# Communication_USB_-_FT232.net
KiCad netlist of a schematic drawn in Altium Designer
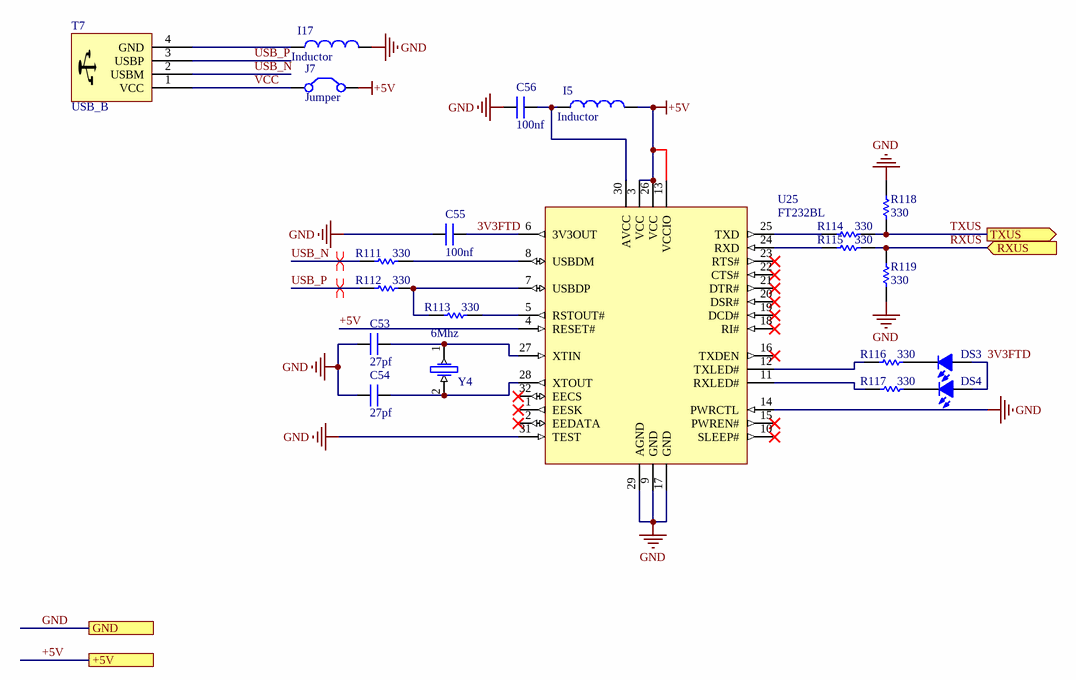
[diagram p0: Communication USB - FT232.SchDoc]

(export (version "E")
  (design (tool "Eeschema 10.0.6"))
  (components
    (comp (ref "C53")
      (value "27pf")
      (footprint "Cap0805")
      (description "Surface mount Capacitor")
      (libsource (lib "PMLIB2020") (part "Cap"))
    )
    (comp (ref "C54")
      (value "27pf")
      (footprint "Cap0805")
      (description "Surface mount Capacitor")
      (libsource (lib "PMLIB2020") (part "Cap"))
    )
    (comp (ref "C55")
      (value "100nf")
      (footprint "Cap0805")
      (description "Surface mount Capacitor")
      (libsource (lib "PMLIB2020") (part "Cap"))
    )
    (comp (ref "C56")
      (value "100nf")
      (footprint "Cap0805")
      (description "Surface mount Capacitor")
      (libsource (lib "PMLIB2020") (part "Cap"))
    )
    (comp (ref "DS3") (value "LED") (footprint "Led0805") (libsource (lib "PMLIB2020") (part "LED")))
    (comp (ref "DS4") (value "LED") (footprint "Led0805") (libsource (lib "PMLIB2020") (part "LED")))
    (comp (ref "I5")
      (value "Inductor")
      (footprint "1206")
      (description "Indicator")
      (libsource (lib "PMLIB2020") (part "Inductor"))
    )
    (comp (ref "I17")
      (value "Inductor")
      (footprint "1206")
      (description "Indicator")
      (libsource (lib "PMLIB2020") (part "Inductor"))
    )
    (comp (ref "J7") (value "Jumper") (footprint "Jumper") (libsource (lib "PMLIB2020-V3") (part "Jumper")))
    (comp (ref "R111")
      (value "330")
      (footprint "R0805")
      (description "Resistor")
      (libsource (lib "PMLIB2020") (part "Resistor"))
    )
    (comp (ref "R112")
      (value "330")
      (footprint "R0805")
      (description "Resistor")
      (libsource (lib "PMLIB2020") (part "Resistor"))
    )
    (comp (ref "R113")
      (value "330")
      (footprint "R0805")
      (description "Resistor")
      (libsource (lib "PMLIB2020") (part "Resistor"))
    )
    (comp (ref "R114")
      (value "330")
      (footprint "R0805")
      (description "Resistor")
      (libsource (lib "PMLIB2020") (part "Resistor"))
    )
    (comp (ref "R115")
      (value "330")
      (footprint "R0805")
      (description "Resistor")
      (libsource (lib "PMLIB2020") (part "Resistor"))
    )
    (comp (ref "R116")
      (value "330")
      (footprint "R0805")
      (description "Resistor")
      (libsource (lib "PMLIB2020") (part "Resistor"))
    )
    (comp (ref "R117")
      (value "330")
      (footprint "R0805")
      (description "Resistor")
      (libsource (lib "PMLIB2020") (part "Resistor"))
    )
    (comp (ref "R118")
      (value "330")
      (footprint "R0805")
      (description "Resistor")
      (libsource (lib "PMLIB2020") (part "Resistor"))
    )
    (comp (ref "R119")
      (value "330")
      (footprint "R0805")
      (description "Resistor")
      (libsource (lib "PMLIB2020") (part "Resistor"))
    )
    (comp (ref "T7")
      (value "USB_B")
      (footprint "USB_Dip_R")
      (description "USB B Connector")
      (libsource (lib "PMLIB2020") (part "USB_B"))
    )
    (comp (ref "U25")
      (value "FT232BL")
      (footprint "LQFP-32_L")
      (description "USB UART Asynchronous Serial Data Transfer Chip, LQFP-32, Pb-Free")
      (libsource (lib "FTDI Communication") (part "FT232BL"))
    )
    (comp (ref "Y4")
      (value "6Mhz")
      (footprint "CrystallB")
      (description "Crystal")
      (libsource (lib "PMLIB2020") (part "Crystal"))
    )
  )
  (nets
    (net (code "1") (name "+5V") (class "Default")
      (node (ref "I5") (pin "2") (pinfunction "2_2") (pintype "passive"))
      (node (ref "J7") (pin "2") (pinfunction "C2_2") (pintype "passive"))
      (node (ref "U25") (pin "13") (pinfunction "VCCIO_13") (pintype "power_in"))
      (node (ref "U25") (pin "26") (pinfunction "VCC_26") (pintype "power_in"))
      (node (ref "U25") (pin "3") (pinfunction "VCC_3") (pintype "power_in"))
      (node (ref "U25") (pin "4") (pinfunction "RESET#_4") (pintype "input"))
    )
    (net (code "2") (name "/3V3FTD") (class "Default")
      (node (ref "C55") (pin "1") (pinfunction "1_1") (pintype "passive"))
      (node (ref "DS3") (pin "A") (pinfunction "A_A") (pintype "passive"))
      (node (ref "DS4") (pin "A") (pinfunction "A_A") (pintype "passive"))
      (node (ref "U25") (pin "6") (pinfunction "3V3OUT_6") (pintype "output"))
    )
    (net (code "3") (name "/RXUS") (class "Default")
      (node (ref "R115") (pin "2") (pinfunction "2_2") (pintype "passive"))
      (node (ref "R119") (pin "2") (pinfunction "2_2") (pintype "passive"))
    )
    (net (code "4") (name "/TXUS") (class "Default")
      (node (ref "R114") (pin "2") (pinfunction "2_2") (pintype "passive"))
      (node (ref "R118") (pin "1") (pinfunction "1_1") (pintype "passive"))
    )
    (net (code "5") (name "/USB_N") (class "Default")
      (node (ref "R111") (pin "1") (pinfunction "1_1") (pintype "passive"))
      (node (ref "T7") (pin "2") (pinfunction "USBM_2") (pintype "passive"))
    )
    (net (code "6") (name "/USB_P") (class "Default")
      (node (ref "R112") (pin "1") (pinfunction "1_1") (pintype "passive"))
      (node (ref "T7") (pin "3") (pinfunction "USBP_3") (pintype "passive"))
    )
    (net (code "7") (name "/VCC") (class "Default")
      (node (ref "J7") (pin "1") (pinfunction "C1_1") (pintype "passive"))
      (node (ref "T7") (pin "1") (pinfunction "VCC_1") (pintype "passive"))
    )
    (net (code "8") (name "GND") (class "Default")
      (node (ref "C53") (pin "1") (pinfunction "1_1") (pintype "passive"))
      (node (ref "C54") (pin "1") (pinfunction "1_1") (pintype "passive"))
      (node (ref "C55") (pin "2") (pinfunction "2_2") (pintype "passive"))
      (node (ref "C56") (pin "2") (pinfunction "2_2") (pintype "passive"))
      (node (ref "I17") (pin "2") (pinfunction "2_2") (pintype "passive"))
      (node (ref "R118") (pin "2") (pinfunction "2_2") (pintype "passive"))
      (node (ref "R119") (pin "1") (pinfunction "1_1") (pintype "passive"))
      (node (ref "U25") (pin "14") (pinfunction "PWRCTL_14") (pintype "input"))
      (node (ref "U25") (pin "17") (pinfunction "GND_17") (pintype "power_in"))
      (node (ref "U25") (pin "29") (pinfunction "AGND_29") (pintype "power_in"))
      (node (ref "U25") (pin "31") (pinfunction "TEST_31") (pintype "input"))
      (node (ref "U25") (pin "9") (pinfunction "GND_9") (pintype "power_in"))
    )
    (net (code "9") (name "Net-(DS3-PadK)") (class "Default")
      (node (ref "DS3") (pin "K") (pinfunction "K_K") (pintype "passive"))
      (node (ref "R116") (pin "2") (pinfunction "2_2") (pintype "passive"))
    )
    (net (code "10") (name "Net-(DS4-PadK)") (class "Default")
      (node (ref "DS4") (pin "K") (pinfunction "K_K") (pintype "passive"))
      (node (ref "R117") (pin "2") (pinfunction "2_2") (pintype "passive"))
    )
    (net (code "11") (name "Net-(T7-GND)") (class "Default")
      (node (ref "I17") (pin "1") (pinfunction "1_1") (pintype "passive"))
      (node (ref "T7") (pin "4") (pinfunction "GND_4") (pintype "passive"))
    )
    (net (code "12") (name "Net-(U25-AVCC)") (class "Default")
      (node (ref "C56") (pin "1") (pinfunction "1_1") (pintype "passive"))
      (node (ref "I5") (pin "1") (pinfunction "1_1") (pintype "passive"))
      (node (ref "U25") (pin "30") (pinfunction "AVCC_30") (pintype "power_in"))
    )
    (net (code "13") (name "Net-(U25-RSTOUT#)") (class "Default")
      (node (ref "R113") (pin "2") (pinfunction "2_2") (pintype "passive"))
      (node (ref "U25") (pin "5") (pinfunction "RSTOUT#_5") (pintype "output"))
    )
    (net (code "14") (name "Net-(U25-RXD)") (class "Default")
      (node (ref "R115") (pin "1") (pinfunction "1_1") (pintype "passive"))
      (node (ref "U25") (pin "24") (pinfunction "RXD_24") (pintype "input"))
    )
    (net (code "15") (name "Net-(U25-RXLED#)") (class "Default")
      (node (ref "R117") (pin "1") (pinfunction "1_1") (pintype "passive"))
      (node (ref "U25") (pin "11") (pinfunction "RXLED#_11") (pintype "open_collector"))
    )
    (net (code "16") (name "Net-(U25-TXD)") (class "Default")
      (node (ref "R114") (pin "1") (pinfunction "1_1") (pintype "passive"))
      (node (ref "U25") (pin "25") (pinfunction "TXD_25") (pintype "output"))
    )
    (net (code "17") (name "Net-(U25-TXLED#)") (class "Default")
      (node (ref "R116") (pin "1") (pinfunction "1_1") (pintype "passive"))
      (node (ref "U25") (pin "12") (pinfunction "TXLED#_12") (pintype "open_collector"))
    )
    (net (code "18") (name "Net-(U25-USBDM)") (class "Default")
      (node (ref "R111") (pin "2") (pinfunction "2_2") (pintype "passive"))
      (node (ref "U25") (pin "8") (pinfunction "USBDM_8") (pintype "bidirectional"))
    )
    (net (code "19") (name "Net-(U25-USBDP)") (class "Default")
      (node (ref "R112") (pin "2") (pinfunction "2_2") (pintype "passive"))
      (node (ref "R113") (pin "1") (pinfunction "1_1") (pintype "passive"))
      (node (ref "U25") (pin "7") (pinfunction "USBDP_7") (pintype "bidirectional"))
    )
    (net (code "20") (name "Net-(U25-XTIN)") (class "Default")
      (node (ref "C53") (pin "2") (pinfunction "2_2") (pintype "passive"))
      (node (ref "U25") (pin "27") (pinfunction "XTIN_27") (pintype "input"))
      (node (ref "Y4") (pin "1") (pinfunction "1_1") (pintype "output"))
    )
    (net (code "21") (name "Net-(U25-XTOUT)") (class "Default")
      (node (ref "C54") (pin "2") (pinfunction "2_2") (pintype "passive"))
      (node (ref "U25") (pin "28") (pinfunction "XTOUT_28") (pintype "output"))
      (node (ref "Y4") (pin "2") (pinfunction "2_2") (pintype "input"))
    )
    (net (code "22") (name "unconnected-(U25-CTS#-Pad22)") (class "Default")
      (node (ref "U25") (pin "22") (pinfunction "CTS#_22") (pintype "input+no_connect"))
    )
    (net (code "23") (name "unconnected-(U25-DCD#-Pad19)") (class "Default")
      (node (ref "U25") (pin "19") (pinfunction "DCD#_19") (pintype "input+no_connect"))
    )
    (net (code "24") (name "unconnected-(U25-DSR#-Pad20)") (class "Default")
      (node (ref "U25") (pin "20") (pinfunction "DSR#_20") (pintype "input+no_connect"))
    )
    (net (code "25") (name "unconnected-(U25-DTR#-Pad21)") (class "Default")
      (node (ref "U25") (pin "21") (pinfunction "DTR#_21") (pintype "output+no_connect"))
    )
    (net (code "26") (name "unconnected-(U25-EECS-Pad32)") (class "Default")
      (node (ref "U25") (pin "32") (pinfunction "EECS_32") (pintype "bidirectional+no_connect"))
    )
    (net (code "27") (name "unconnected-(U25-EEDATA-Pad2)") (class "Default")
      (node (ref "U25") (pin "2") (pinfunction "EEDATA_2") (pintype "bidirectional+no_connect"))
    )
    (net (code "28") (name "unconnected-(U25-EESK-Pad1)") (class "Default")
      (node (ref "U25") (pin "1") (pinfunction "EESK_1") (pintype "output+no_connect"))
    )
    (net (code "29") (name "unconnected-(U25-PWREN#-Pad15)") (class "Default")
      (node (ref "U25") (pin "15") (pinfunction "PWREN#_15") (pintype "output+no_connect"))
    )
    (net (code "30") (name "unconnected-(U25-RI#-Pad18)") (class "Default")
      (node (ref "U25") (pin "18") (pinfunction "RI#_18") (pintype "input+no_connect"))
    )
    (net (code "31") (name "unconnected-(U25-RTS#-Pad23)") (class "Default")
      (node (ref "U25") (pin "23") (pinfunction "RTS#_23") (pintype "output+no_connect"))
    )
    (net (code "32") (name "unconnected-(U25-SLEEP#-Pad10)") (class "Default")
      (node (ref "U25") (pin "10") (pinfunction "SLEEP#_10") (pintype "output+no_connect"))
    )
    (net (code "33") (name "unconnected-(U25-TXDEN-Pad16)") (class "Default")
      (node (ref "U25") (pin "16") (pinfunction "TXDEN_16") (pintype "output+no_connect"))
    )
  )
)
